# Sheet1.net
KiCad netlist of a schematic drawn in Altium Designer
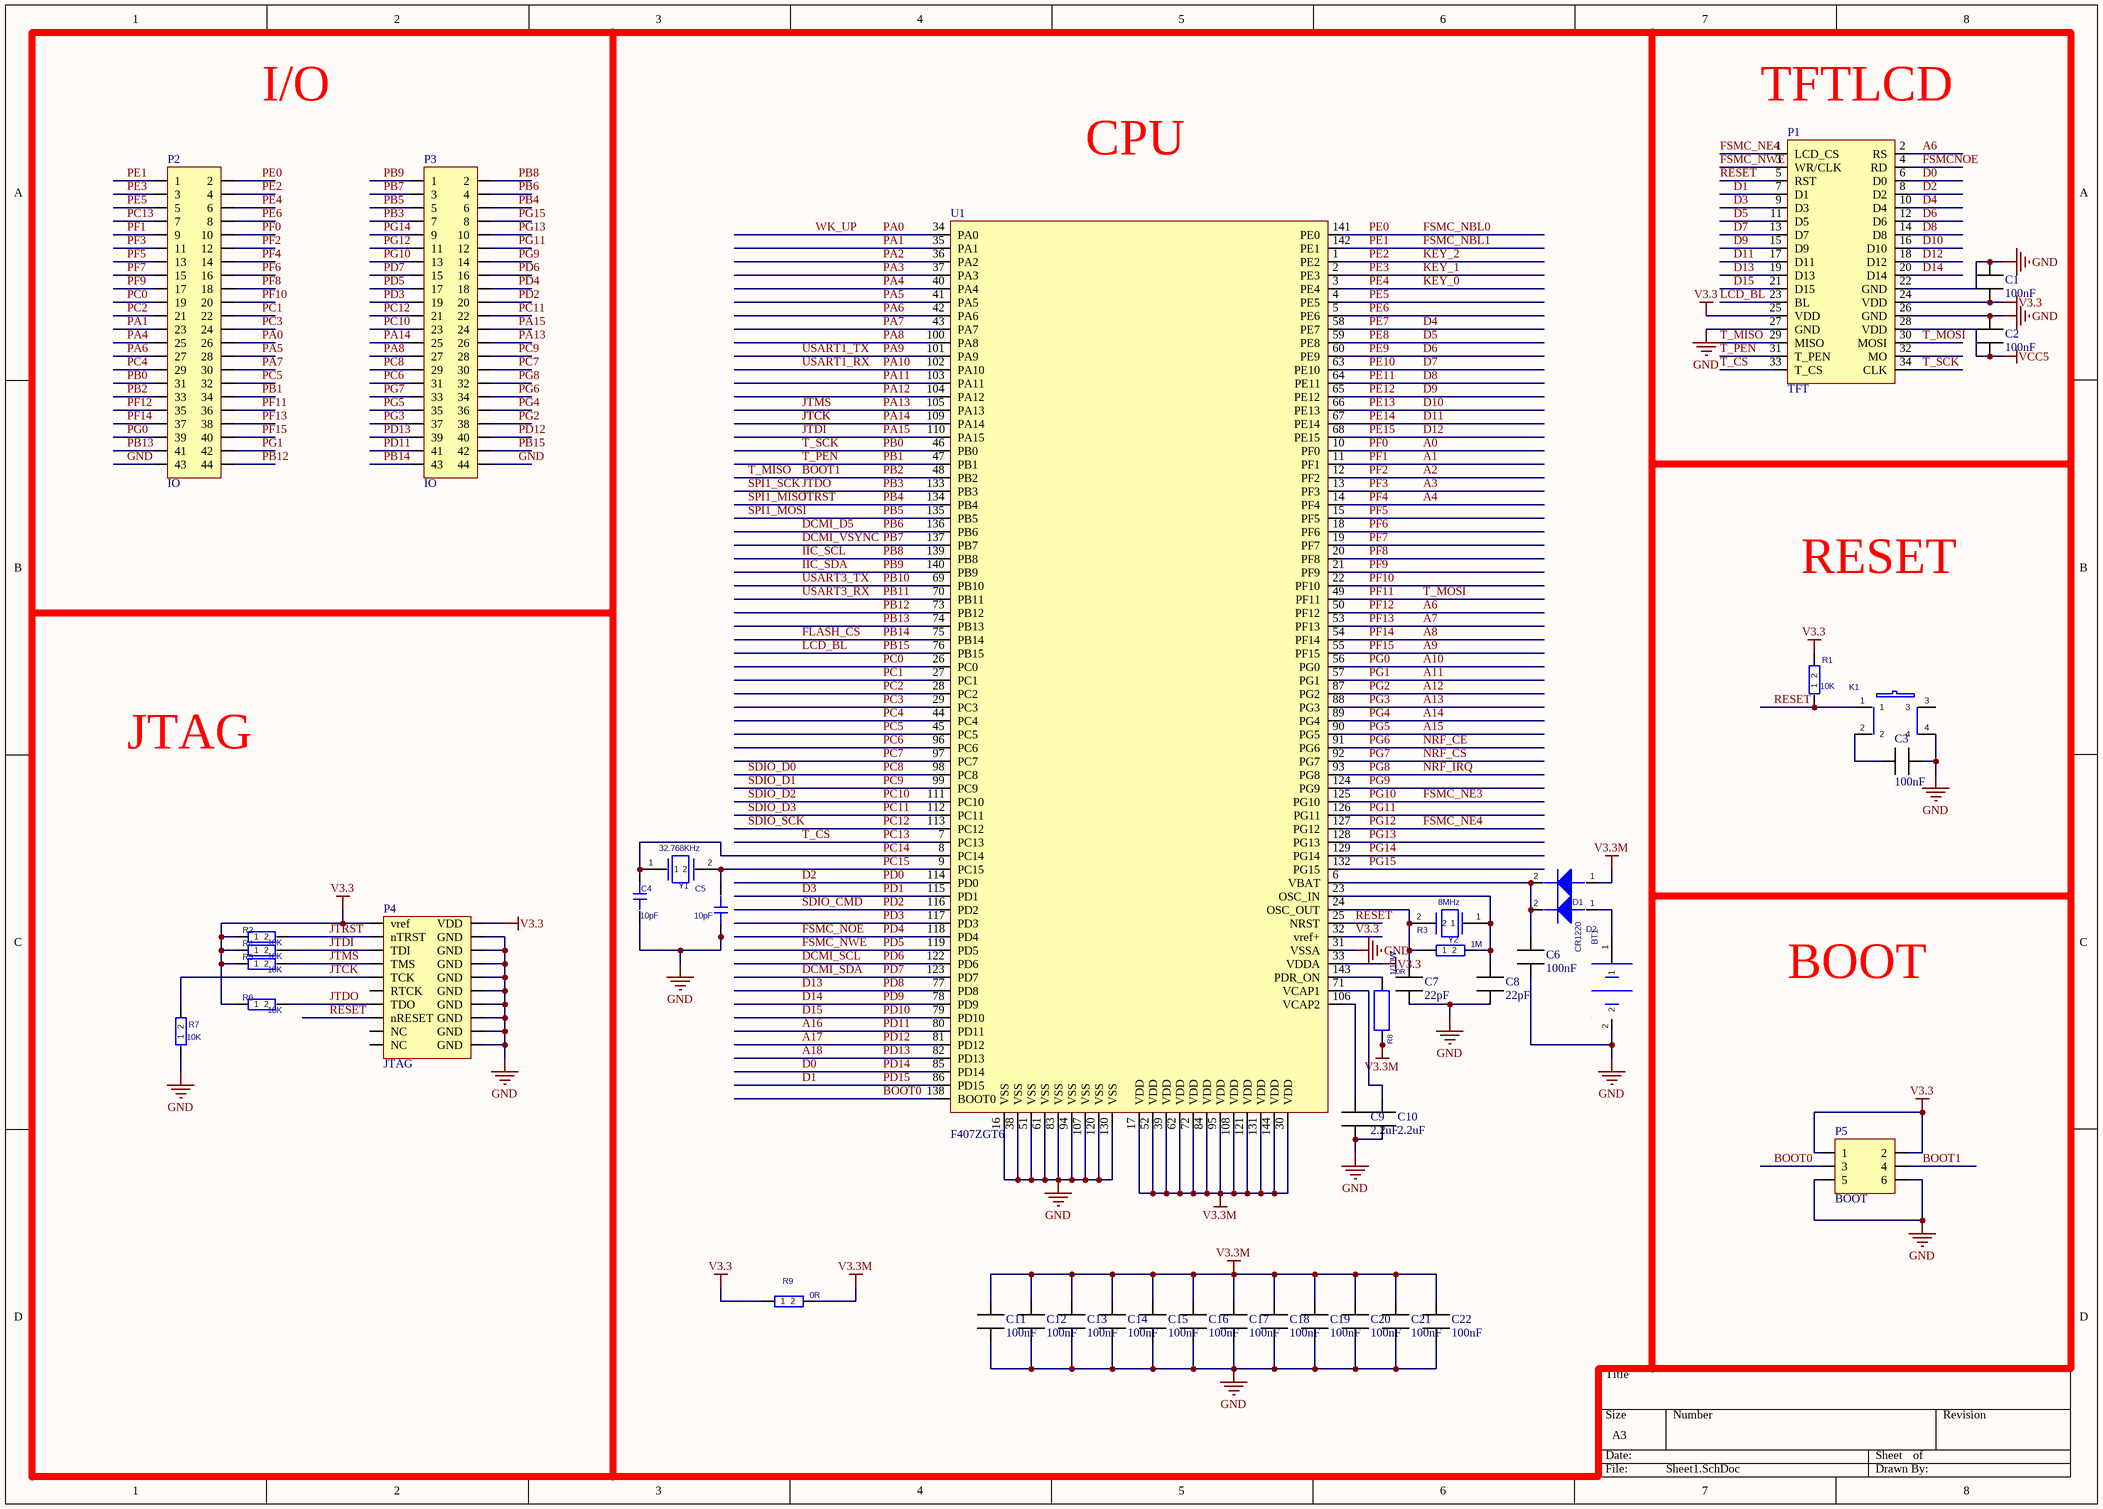
[diagram p0: Sheet1.SchDoc]

(export (version "E")
  (design (tool "Eeschema 10.0.6"))
  (components
    (comp (ref "BT1") (value "CR1220") (footprint "BATERY") (libsource (lib "F407ZGT6") (part "CR1220")))
    (comp (ref "C1") (value "100nF") (footprint "CAP_0603_FIRE") (libsource (lib "F407ZGT6") (part "CAP")))
    (comp (ref "C2") (value "100nF") (footprint "CAP_0603_FIRE") (libsource (lib "F407ZGT6") (part "CAP")))
    (comp (ref "C3") (value "100nF") (footprint "CAP_0603_FIRE") (libsource (lib "F407ZGT6") (part "CAP")))
    (comp (ref "C4")
      (value "10pF")
      (footprint "CAP_0603_FIRE")
      (description "SURFACE MOUNT CAPACITOR 0.031 X 0.061 INCHES")
      (fields (field (name "Comment") "CAP_0.1UF_0603_FIRE"))
      (libsource (lib "F407ZGT6") (part "CAP_0.1UF_0603_FIRE"))
    )
    (comp (ref "C5")
      (value "10pF")
      (footprint "CAP_0603_FIRE")
      (description "SURFACE MOUNT CAPACITOR 0.031 X 0.061 INCHES")
      (fields (field (name "Comment") "CAP_0.1UF_0603_FIRE"))
      (libsource (lib "F407ZGT6") (part "CAP_0.1UF_0603_FIRE"))
    )
    (comp (ref "C6") (value "100nF") (footprint "CAP_0603_FIRE") (libsource (lib "F407ZGT6") (part "CAP")))
    (comp (ref "C7") (value "22pF") (footprint "CAP_0603_FIRE") (libsource (lib "F407ZGT6") (part "CAP")))
    (comp (ref "C8") (value "22pF") (footprint "CAP_0603_FIRE") (libsource (lib "F407ZGT6") (part "CAP")))
    (comp (ref "C9") (value "2.2uF") (footprint "CAP_0603_FIRE") (libsource (lib "F407ZGT6") (part "CAP")))
    (comp (ref "C10") (value "2.2uF") (footprint "CAP_0603_FIRE") (libsource (lib "F407ZGT6") (part "CAP")))
    (comp (ref "C11") (value "100nF") (footprint "CAP_0603_FIRE") (libsource (lib "F407ZGT6") (part "CAP")))
    (comp (ref "C12") (value "100nF") (footprint "CAP_0603_FIRE") (libsource (lib "F407ZGT6") (part "CAP")))
    (comp (ref "C13") (value "100nF") (footprint "CAP_0603_FIRE") (libsource (lib "F407ZGT6") (part "CAP")))
    (comp (ref "C14") (value "100nF") (footprint "CAP_0603_FIRE") (libsource (lib "F407ZGT6") (part "CAP")))
    (comp (ref "C15") (value "100nF") (footprint "CAP_0603_FIRE") (libsource (lib "F407ZGT6") (part "CAP")))
    (comp (ref "C16") (value "100nF") (footprint "CAP_0603_FIRE") (libsource (lib "F407ZGT6") (part "CAP")))
    (comp (ref "C17") (value "100nF") (footprint "CAP_0603_FIRE") (libsource (lib "F407ZGT6") (part "CAP")))
    (comp (ref "C18") (value "100nF") (footprint "CAP_0603_FIRE") (libsource (lib "F407ZGT6") (part "CAP")))
    (comp (ref "C19") (value "100nF") (footprint "CAP_0603_FIRE") (libsource (lib "F407ZGT6") (part "CAP")))
    (comp (ref "C20") (value "100nF") (footprint "CAP_0603_FIRE") (libsource (lib "F407ZGT6") (part "CAP")))
    (comp (ref "C21") (value "100nF") (footprint "CAP_0603_FIRE") (libsource (lib "F407ZGT6") (part "CAP")))
    (comp (ref "C22") (value "100nF") (footprint "CAP_0603_FIRE") (libsource (lib "F407ZGT6") (part "CAP")))
    (comp (ref "D1") (value "IN4148") (footprint "DIODE_SOP") (libsource (lib "F407ZGT6") (part "IN4148")))
    (comp (ref "D2") (value "IN4148") (footprint "DIODE_SOP") (libsource (lib "F407ZGT6") (part "IN4148")))
    (comp (ref "K1") (value "KEY") (footprint "SW6.2/6.2-SMD") (libsource (lib "F407ZGT6") (part "KEY")))
    (comp (ref "P1") (value "TFT") (footprint "TFT") (libsource (lib "F407ZGT6") (part "TFT")))
    (comp (ref "P2") (value "IO") (footprint "HEAD2*22") (libsource (lib "F407ZGT6") (part "IO")))
    (comp (ref "P3") (value "IO") (footprint "HEAD2*22") (libsource (lib "F407ZGT6") (part "IO")))
    (comp (ref "P4") (value "JTAG") (footprint "FC20H") (libsource (lib "F407ZGT6") (part "JTAG")))
    (comp (ref "P5") (value "BOOT") (footprint "BOOT") (libsource (lib "F407ZGT6") (part "BOOT")))
    (comp (ref "R1")
      (value "10K")
      (footprint "RES_0603_FIRE")
      (description "0402")
      (fields (field (name "TOLERANCE") "+-5%") (field (name "Comment") "RES_1K_0603_FIRE"))
      (libsource (lib "F407ZGT6") (part "RES_1K_0603_FIRE"))
    )
    (comp (ref "R2")
      (value "10K")
      (footprint "RES_0603_FIRE")
      (description "SURFACE MOUNT RESISTOR 0.031 X 0.061 INCHES, 1/10W")
      (fields (field (name "Comment") "RES_10K_0603_FIRE"))
      (libsource (lib "F407ZGT6") (part "RES_10K_0603_FIRE"))
    )
    (comp (ref "R3")
      (value "1M")
      (footprint "RES_0603_FIRE")
      (description "0402")
      (fields (field (name "TOLERANCE") "+-5%") (field (name "Comment") "RES_1K_0603_FIRE"))
      (libsource (lib "F407ZGT6") (part "RES_1K_0603_FIRE"))
    )
    (comp (ref "R4")
      (value "10K")
      (footprint "RES_0603_FIRE")
      (description "SURFACE MOUNT RESISTOR 0.031 X 0.061 INCHES, 1/10W")
      (fields (field (name "Comment") "RES_10K_0603_FIRE"))
      (libsource (lib "F407ZGT6") (part "RES_10K_0603_FIRE"))
    )
    (comp (ref "R5")
      (value "10K")
      (footprint "RES_0603_FIRE")
      (description "SURFACE MOUNT RESISTOR 0.031 X 0.061 INCHES, 1/10W")
      (fields (field (name "Comment") "RES_10K_0603_FIRE"))
      (libsource (lib "F407ZGT6") (part "RES_10K_0603_FIRE"))
    )
    (comp (ref "R6")
      (value "10K")
      (footprint "RES_0603_FIRE")
      (description "SURFACE MOUNT RESISTOR 0.031 X 0.061 INCHES, 1/10W")
      (fields (field (name "Comment") "RES_10K_0603_FIRE"))
      (libsource (lib "F407ZGT6") (part "RES_10K_0603_FIRE"))
    )
    (comp (ref "R7")
      (value "10K")
      (footprint "RES_0603_FIRE")
      (description "SURFACE MOUNT RESISTOR 0.031 X 0.061 INCHES, 1/10W")
      (fields (field (name "Comment") "RES_10K_0603_FIRE"))
      (libsource (lib "F407ZGT6") (part "RES_10K_0603_FIRE"))
    )
    (comp (ref "R8")
      (value "0R")
      (footprint "0603")
      (description "0603, 50V, 1/10W, 5%")
      (fields
        (field (name "PART_NUMBER") "RE200045-01")
        (field (name "MFR_PART_NUMBER") "RS03K104JT")
        (field (name "POWER") "1/10W")
      )
      (libsource (lib "F407ZGT6") (part "RES-0603-0R"))
    )
    (comp (ref "R9")
      (value "0R")
      (footprint "RES_0603_FIRE")
      (description "0402")
      (fields (field (name "TOLERANCE") "+-5%") (field (name "Comment") "RES_1K_0603_FIRE"))
      (libsource (lib "F407ZGT6") (part "RES_1K_0603_FIRE"))
    )
    (comp (ref "U1")
      (value "F407ZGT6")
      (footprint "STM32F407ZGT6")
      (libsource (lib "F407ZGT6") (part "F407ZGT6"))
    )
    (comp (ref "Y1")
      (value "32.768KHz")
      (footprint "CRYS-3X8")
      (description "CRYSTAL")
      (fields (field (name "Comment") "XTAL_32.768KHZ_FIRE"))
      (libsource (lib "F407ZGT6") (part "XTAL_32.768KHZ_FIRE"))
    )
    (comp (ref "Y2")
      (value "8MHz")
      (footprint "CRYSTAL_SMD_FIRE")
      (description "CRYSTAL")
      (fields (field (name "Comment") "XTAL_8M_FIRE"))
      (libsource (lib "F407ZGT6") (part "XTAL_8M_FIRE"))
    )
  )
  (nets
    (net (code "1") (name "/A0") (class "Default")
      (node (ref "P2") (pin "10") (pinfunction "10_10") (pintype "passive"))
      (node (ref "U1") (pin "10") (pinfunction "PF0_10") (pintype "passive"))
    )
    (net (code "2") (name "/A1") (class "Default")
      (node (ref "P2") (pin "9") (pinfunction "9_9") (pintype "passive"))
      (node (ref "U1") (pin "11") (pinfunction "PF1_11") (pintype "passive"))
    )
    (net (code "3") (name "/A2") (class "Default")
      (node (ref "P2") (pin "12") (pinfunction "12_12") (pintype "passive"))
      (node (ref "U1") (pin "12") (pinfunction "PF2_12") (pintype "passive"))
    )
    (net (code "4") (name "/A3") (class "Default")
      (node (ref "P2") (pin "11") (pinfunction "11_11") (pintype "passive"))
      (node (ref "U1") (pin "13") (pinfunction "PF3_13") (pintype "passive"))
    )
    (net (code "5") (name "/A4") (class "Default")
      (node (ref "P2") (pin "14") (pinfunction "14_14") (pintype "passive"))
      (node (ref "U1") (pin "14") (pinfunction "PF4_14") (pintype "passive"))
    )
    (net (code "6") (name "/A6") (class "Default")
      (node (ref "P1") (pin "2") (pinfunction "RS_2") (pintype "passive"))
      (node (ref "P2") (pin "35") (pinfunction "35_35") (pintype "passive"))
      (node (ref "U1") (pin "50") (pinfunction "PF12_50") (pintype "passive"))
    )
    (net (code "7") (name "/A7") (class "Default")
      (node (ref "P2") (pin "38") (pinfunction "38_38") (pintype "passive"))
      (node (ref "U1") (pin "53") (pinfunction "PF13_53") (pintype "passive"))
    )
    (net (code "8") (name "/A8") (class "Default")
      (node (ref "P2") (pin "37") (pinfunction "37_37") (pintype "passive"))
      (node (ref "U1") (pin "54") (pinfunction "PF14_54") (pintype "passive"))
    )
    (net (code "9") (name "/A9") (class "Default")
      (node (ref "P2") (pin "40") (pinfunction "40_40") (pintype "passive"))
      (node (ref "U1") (pin "55") (pinfunction "PF15_55") (pintype "passive"))
    )
    (net (code "10") (name "/A10") (class "Default")
      (node (ref "P2") (pin "39") (pinfunction "39_39") (pintype "passive"))
      (node (ref "U1") (pin "56") (pinfunction "PG0_56") (pintype "passive"))
    )
    (net (code "11") (name "/A11") (class "Default")
      (node (ref "P2") (pin "42") (pinfunction "42_42") (pintype "passive"))
      (node (ref "U1") (pin "57") (pinfunction "PG1_57") (pintype "passive"))
    )
    (net (code "12") (name "/A12") (class "Default")
      (node (ref "P3") (pin "38") (pinfunction "38_38") (pintype "passive"))
      (node (ref "U1") (pin "87") (pinfunction "PG2_87") (pintype "passive"))
    )
    (net (code "13") (name "/A13") (class "Default")
      (node (ref "P3") (pin "37") (pinfunction "37_37") (pintype "passive"))
      (node (ref "U1") (pin "88") (pinfunction "PG3_88") (pintype "passive"))
    )
    (net (code "14") (name "/A14") (class "Default")
      (node (ref "P3") (pin "36") (pinfunction "36_36") (pintype "passive"))
      (node (ref "U1") (pin "89") (pinfunction "PG4_89") (pintype "passive"))
    )
    (net (code "15") (name "/A15") (class "Default")
      (node (ref "P3") (pin "35") (pinfunction "35_35") (pintype "passive"))
      (node (ref "U1") (pin "90") (pinfunction "PG5_90") (pintype "passive"))
    )
    (net (code "16") (name "/A16") (class "Default")
      (node (ref "P3") (pin "41") (pinfunction "41_41") (pintype "passive"))
      (node (ref "U1") (pin "80") (pinfunction "PD11_80") (pintype "passive"))
    )
    (net (code "17") (name "/A17") (class "Default")
      (node (ref "P3") (pin "40") (pinfunction "40_40") (pintype "passive"))
      (node (ref "U1") (pin "81") (pinfunction "PD12_81") (pintype "passive"))
    )
    (net (code "18") (name "/A18") (class "Default")
      (node (ref "P3") (pin "39") (pinfunction "39_39") (pintype "passive"))
      (node (ref "U1") (pin "82") (pinfunction "PD13_82") (pintype "passive"))
    )
    (net (code "19") (name "/BOOT0") (class "Default")
      (node (ref "P5") (pin "3") (pinfunction "3_3") (pintype "passive"))
      (node (ref "U1") (pin "138") (pinfunction "BOOT0_138") (pintype "passive"))
    )
    (net (code "20") (name "/BOOT1") (class "Default")
      (node (ref "P1") (pin "29") (pinfunction "MISO_29") (pintype "passive"))
      (node (ref "P2") (pin "33") (pinfunction "33_33") (pintype "passive"))
      (node (ref "P5") (pin "4") (pinfunction "4_4") (pintype "passive"))
      (node (ref "U1") (pin "48") (pinfunction "PB2_48") (pintype "passive"))
    )
    (net (code "21") (name "/D0") (class "Default")
      (node (ref "P1") (pin "6") (pinfunction "D0_6") (pintype "passive"))
      (node (ref "U1") (pin "85") (pinfunction "PD14_85") (pintype "passive"))
    )
    (net (code "22") (name "/D1") (class "Default")
      (node (ref "P1") (pin "7") (pinfunction "D1_7") (pintype "passive"))
      (node (ref "U1") (pin "86") (pinfunction "PD15_86") (pintype "passive"))
    )
    (net (code "23") (name "/D2") (class "Default")
      (node (ref "P1") (pin "8") (pinfunction "D2_8") (pintype "passive"))
      (node (ref "U1") (pin "114") (pinfunction "PD0_114") (pintype "passive"))
    )
    (net (code "24") (name "/D3") (class "Default")
      (node (ref "P1") (pin "9") (pinfunction "D3_9") (pintype "passive"))
      (node (ref "U1") (pin "115") (pinfunction "PD1_115") (pintype "passive"))
    )
    (net (code "25") (name "/D4") (class "Default")
      (node (ref "P1") (pin "10") (pinfunction "D4_10") (pintype "passive"))
      (node (ref "U1") (pin "58") (pinfunction "PE7_58") (pintype "passive"))
    )
    (net (code "26") (name "/D5") (class "Default")
      (node (ref "P1") (pin "11") (pinfunction "D5_11") (pintype "passive"))
      (node (ref "U1") (pin "59") (pinfunction "PE8_59") (pintype "passive"))
    )
    (net (code "27") (name "/D6") (class "Default")
      (node (ref "P1") (pin "12") (pinfunction "D6_12") (pintype "passive"))
      (node (ref "U1") (pin "60") (pinfunction "PE9_60") (pintype "passive"))
    )
    (net (code "28") (name "/D7") (class "Default")
      (node (ref "P1") (pin "13") (pinfunction "D7_13") (pintype "passive"))
      (node (ref "U1") (pin "63") (pinfunction "PE10_63") (pintype "passive"))
    )
    (net (code "29") (name "/D8") (class "Default")
      (node (ref "P1") (pin "14") (pinfunction "D8_14") (pintype "passive"))
      (node (ref "U1") (pin "64") (pinfunction "PE11_64") (pintype "passive"))
    )
    (net (code "30") (name "/D9") (class "Default")
      (node (ref "P1") (pin "15") (pinfunction "D9_15") (pintype "passive"))
      (node (ref "U1") (pin "65") (pinfunction "PE12_65") (pintype "passive"))
    )
    (net (code "31") (name "/D10") (class "Default")
      (node (ref "P1") (pin "16") (pinfunction "D10_16") (pintype "passive"))
      (node (ref "U1") (pin "66") (pinfunction "PE13_66") (pintype "passive"))
    )
    (net (code "32") (name "/D11") (class "Default")
      (node (ref "P1") (pin "17") (pinfunction "D11_17") (pintype "passive"))
      (node (ref "U1") (pin "67") (pinfunction "PE14_67") (pintype "passive"))
    )
    (net (code "33") (name "/D12") (class "Default")
      (node (ref "P1") (pin "18") (pinfunction "D12_18") (pintype "passive"))
      (node (ref "U1") (pin "68") (pinfunction "PE15_68") (pintype "passive"))
    )
    (net (code "34") (name "/D13") (class "Default")
      (node (ref "P1") (pin "19") (pinfunction "D13_19") (pintype "passive"))
      (node (ref "U1") (pin "77") (pinfunction "PD8_77") (pintype "passive"))
    )
    (net (code "35") (name "/D14") (class "Default")
      (node (ref "P1") (pin "20") (pinfunction "D14_20") (pintype "passive"))
      (node (ref "U1") (pin "78") (pinfunction "PD9_78") (pintype "passive"))
    )
    (net (code "36") (name "/D15") (class "Default")
      (node (ref "P1") (pin "21") (pinfunction "D15_21") (pintype "passive"))
      (node (ref "U1") (pin "79") (pinfunction "PD10_79") (pintype "passive"))
    )
    (net (code "37") (name "/DCMI_D5") (class "Default")
      (node (ref "P3") (pin "4") (pinfunction "4_4") (pintype "passive"))
      (node (ref "U1") (pin "136") (pinfunction "PB6_136") (pintype "passive"))
    )
    (net (code "38") (name "/DCMI_SCL") (class "Default")
      (node (ref "P3") (pin "16") (pinfunction "16_16") (pintype "passive"))
      (node (ref "U1") (pin "122") (pinfunction "PD6_122") (pintype "passive"))
    )
    (net (code "39") (name "/DCMI_SDA") (class "Default")
      (node (ref "P3") (pin "15") (pinfunction "15_15") (pintype "passive"))
      (node (ref "U1") (pin "123") (pinfunction "PD7_123") (pintype "passive"))
    )
    (net (code "40") (name "/DCMI_VSYNC") (class "Default")
      (node (ref "P3") (pin "3") (pinfunction "3_3") (pintype "passive"))
      (node (ref "U1") (pin "137") (pinfunction "PB7_137") (pintype "passive"))
    )
    (net (code "41") (name "/FLASH_CS") (class "Default")
      (node (ref "P3") (pin "43") (pinfunction "43_43") (pintype "passive"))
      (node (ref "U1") (pin "75") (pinfunction "PB14_75") (pintype "passive"))
    )
    (net (code "42") (name "/FSMCNOE") (class "Default")
      (node (ref "P1") (pin "4") (pinfunction "RD_4") (pintype "passive"))
    )
    (net (code "43") (name "/FSMC_NBL0") (class "Default")
      (node (ref "P2") (pin "2") (pinfunction "2_2") (pintype "passive"))
      (node (ref "U1") (pin "141") (pinfunction "PE0_141") (pintype "passive"))
    )
    (net (code "44") (name "/FSMC_NBL1") (class "Default")
      (node (ref "P2") (pin "1") (pinfunction "1_1") (pintype "passive"))
      (node (ref "U1") (pin "142") (pinfunction "PE1_142") (pintype "passive"))
    )
    (net (code "45") (name "/FSMC_NE3") (class "Default")
      (node (ref "P3") (pin "13") (pinfunction "13_13") (pintype "passive"))
      (node (ref "U1") (pin "125") (pinfunction "PG10_125") (pintype "passive"))
    )
    (net (code "46") (name "/FSMC_NE4") (class "Default")
      (node (ref "P1") (pin "1") (pinfunction "LCD_CS_1") (pintype "passive"))
      (node (ref "P3") (pin "11") (pinfunction "11_11") (pintype "passive"))
      (node (ref "U1") (pin "127") (pinfunction "PG12_127") (pintype "passive"))
    )
    (net (code "47") (name "/FSMC_NOE") (class "Default")
      (node (ref "P3") (pin "18") (pinfunction "18_18") (pintype "passive"))
      (node (ref "U1") (pin "118") (pinfunction "PD4_118") (pintype "passive"))
    )
    (net (code "48") (name "/FSMC_NWE") (class "Default")
      (node (ref "P1") (pin "3") (pinfunction "WR/CLK_3") (pintype "passive"))
      (node (ref "P3") (pin "17") (pinfunction "17_17") (pintype "passive"))
      (node (ref "U1") (pin "119") (pinfunction "PD5_119") (pintype "passive"))
    )
    (net (code "49") (name "/IIC_SCL") (class "Default")
      (node (ref "P3") (pin "2") (pinfunction "2_2") (pintype "passive"))
      (node (ref "U1") (pin "139") (pinfunction "PB8_139") (pintype "passive"))
    )
    (net (code "50") (name "/IIC_SDA") (class "Default")
      (node (ref "P3") (pin "1") (pinfunction "1_1") (pintype "passive"))
      (node (ref "U1") (pin "140") (pinfunction "PB9_140") (pintype "passive"))
    )
    (net (code "51") (name "/JTCK") (class "Default")
      (node (ref "P3") (pin "25") (pinfunction "25_25") (pintype "passive"))
      (node (ref "P4") (pin "9") (pinfunction "TCK_9") (pintype "passive"))
      (node (ref "R7") (pin "2") (pinfunction "2_2") (pintype "passive"))
      (node (ref "U1") (pin "109") (pinfunction "PA14_109") (pintype "passive"))
    )
    (net (code "52") (name "/JTDI") (class "Default")
      (node (ref "P3") (pin "24") (pinfunction "24_24") (pintype "passive"))
      (node (ref "P4") (pin "5") (pinfunction "TDI_5") (pintype "passive"))
      (node (ref "R4") (pin "2") (pinfunction "2_2") (pintype "passive"))
      (node (ref "U1") (pin "110") (pinfunction "PA15_110") (pintype "passive"))
    )
    (net (code "53") (name "/JTDO") (class "Default")
      (node (ref "P3") (pin "7") (pinfunction "7_7") (pintype "passive"))
      (node (ref "P4") (pin "13") (pinfunction "TDO_13") (pintype "passive"))
      (node (ref "R6") (pin "2") (pinfunction "2_2") (pintype "passive"))
      (node (ref "U1") (pin "133") (pinfunction "PB3_133") (pintype "passive"))
    )
    (net (code "54") (name "/JTMS") (class "Default")
      (node (ref "P3") (pin "26") (pinfunction "26_26") (pintype "passive"))
      (node (ref "P4") (pin "7") (pinfunction "TMS_7") (pintype "passive"))
      (node (ref "R5") (pin "2") (pinfunction "2_2") (pintype "passive"))
      (node (ref "U1") (pin "105") (pinfunction "PA13_105") (pintype "passive"))
    )
    (net (code "55") (name "/JTRST") (class "Default")
      (node (ref "P3") (pin "6") (pinfunction "6_6") (pintype "passive"))
      (node (ref "P4") (pin "3") (pinfunction "nTRST_3") (pintype "passive"))
      (node (ref "R2") (pin "2") (pinfunction "2_2") (pintype "passive"))
      (node (ref "U1") (pin "134") (pinfunction "PB4_134") (pintype "passive"))
    )
    (net (code "56") (name "/KEY_0") (class "Default")
      (node (ref "P2") (pin "6") (pinfunction "6_6") (pintype "passive"))
      (node (ref "U1") (pin "3") (pinfunction "PE4_3") (pintype "passive"))
    )
    (net (code "57") (name "/KEY_1") (class "Default")
      (node (ref "P2") (pin "3") (pinfunction "3_3") (pintype "passive"))
      (node (ref "U1") (pin "2") (pinfunction "PE3_2") (pintype "passive"))
    )
    (net (code "58") (name "/KEY_2") (class "Default")
      (node (ref "P2") (pin "4") (pinfunction "4_4") (pintype "passive"))
      (node (ref "U1") (pin "1") (pinfunction "PE2_1") (pintype "passive"))
    )
    (net (code "59") (name "/LCD_BL") (class "Default")
      (node (ref "P1") (pin "23") (pinfunction "BL_23") (pintype "passive"))
      (node (ref "P3") (pin "42") (pinfunction "42_42") (pintype "passive"))
      (node (ref "U1") (pin "76") (pinfunction "PB15_76") (pintype "passive"))
    )
    (net (code "60") (name "/NRF_CE") (class "Default")
      (node (ref "P3") (pin "34") (pinfunction "34_34") (pintype "passive"))
      (node (ref "U1") (pin "91") (pinfunction "PG6_91") (pintype "passive"))
    )
    (net (code "61") (name "/NRF_CS") (class "Default")
      (node (ref "P3") (pin "33") (pinfunction "33_33") (pintype "passive"))
      (node (ref "U1") (pin "92") (pinfunction "PG7_92") (pintype "passive"))
    )
    (net (code "62") (name "/NRF_IRQ") (class "Default")
      (node (ref "P3") (pin "32") (pinfunction "32_32") (pintype "passive"))
      (node (ref "U1") (pin "93") (pinfunction "PG8_93") (pintype "passive"))
    )
    (net (code "63") (name "/PA0") (class "Default")
      (node (ref "P2") (pin "26") (pinfunction "26_26") (pintype "passive"))
      (node (ref "U1") (pin "34") (pinfunction "PA0_34") (pintype "passive"))
    )
    (net (code "64") (name "/PA1") (class "Default")
      (node (ref "P2") (pin "23") (pinfunction "23_23") (pintype "passive"))
      (node (ref "U1") (pin "35") (pinfunction "PA1_35") (pintype "passive"))
    )
    (net (code "65") (name "/PA2") (class "Default")
      (node (ref "U1") (pin "36") (pinfunction "PA2_36") (pintype "passive"))
    )
    (net (code "66") (name "/PA3") (class "Default")
      (node (ref "U1") (pin "37") (pinfunction "PA3_37") (pintype "passive"))
    )
    (net (code "67") (name "/PA4") (class "Default")
      (node (ref "P2") (pin "25") (pinfunction "25_25") (pintype "passive"))
      (node (ref "U1") (pin "40") (pinfunction "PA4_40") (pintype "passive"))
    )
    (net (code "68") (name "/PA5") (class "Default")
      (node (ref "P2") (pin "28") (pinfunction "28_28") (pintype "passive"))
      (node (ref "U1") (pin "41") (pinfunction "PA5_41") (pintype "passive"))
    )
    (net (code "69") (name "/PA6") (class "Default")
      (node (ref "P2") (pin "27") (pinfunction "27_27") (pintype "passive"))
      (node (ref "U1") (pin "42") (pinfunction "PA6_42") (pintype "passive"))
    )
    (net (code "70") (name "/PA7") (class "Default")
      (node (ref "P2") (pin "30") (pinfunction "30_30") (pintype "passive"))
      (node (ref "U1") (pin "43") (pinfunction "PA7_43") (pintype "passive"))
    )
    (net (code "71") (name "/PA8") (class "Default")
      (node (ref "P3") (pin "27") (pinfunction "27_27") (pintype "passive"))
      (node (ref "U1") (pin "100") (pinfunction "PA8_100") (pintype "passive"))
    )
    (net (code "72") (name "/PA9") (class "Default")
      (node (ref "U1") (pin "101") (pinfunction "PA9_101") (pintype "passive"))
    )
    (net (code "73") (name "/PA10") (class "Default")
      (node (ref "U1") (pin "102") (pinfunction "PA10_102") (pintype "passive"))
    )
    (net (code "74") (name "/PA11") (class "Default")
      (node (ref "U1") (pin "103") (pinfunction "PA11_103") (pintype "passive"))
    )
    (net (code "75") (name "/PA12") (class "Default")
      (node (ref "U1") (pin "104") (pinfunction "PA12_104") (pintype "passive"))
    )
    (net (code "76") (name "/PB0") (class "Default")
      (node (ref "P1") (pin "34") (pinfunction "CLK_34") (pintype "passive"))
      (node (ref "P2") (pin "31") (pinfunction "31_31") (pintype "passive"))
      (node (ref "U1") (pin "46") (pinfunction "PB0_46") (pintype "passive"))
    )
    (net (code "77") (name "/PB1") (class "Default")
      (node (ref "P1") (pin "31") (pinfunction "T_PEN_31") (pintype "passive"))
      (node (ref "P2") (pin "34") (pinfunction "34_34") (pintype "passive"))
      (node (ref "U1") (pin "47") (pinfunction "PB1_47") (pintype "passive"))
    )
    (net (code "78") (name "/PB5") (class "Default")
      (node (ref "P3") (pin "5") (pinfunction "5_5") (pintype "passive"))
      (node (ref "U1") (pin "135") (pinfunction "PB5_135") (pintype "passive"))
    )
    (net (code "79") (name "/PB10") (class "Default")
      (node (ref "U1") (pin "69") (pinfunction "PB10_69") (pintype "passive"))
    )
    (net (code "80") (name "/PB11") (class "Default")
      (node (ref "U1") (pin "70") (pinfunction "PB11_70") (pintype "passive"))
    )
    (net (code "81") (name "/PB12") (class "Default")
      (node (ref "P2") (pin "44") (pinfunction "44_44") (pintype "passive"))
      (node (ref "U1") (pin "73") (pinfunction "PB12_73") (pintype "passive"))
    )
    (net (code "82") (name "/PB13") (class "Default")
      (node (ref "P2") (pin "41") (pinfunction "41_41") (pintype "passive"))
      (node (ref "U1") (pin "74") (pinfunction "PB13_74") (pintype "passive"))
    )
    (net (code "83") (name "/PC0") (class "Default")
      (node (ref "P2") (pin "19") (pinfunction "19_19") (pintype "passive"))
      (node (ref "U1") (pin "26") (pinfunction "PC0_26") (pintype "passive"))
    )
    (net (code "84") (name "/PC1") (class "Default")
      (node (ref "P2") (pin "22") (pinfunction "22_22") (pintype "passive"))
      (node (ref "U1") (pin "27") (pinfunction "PC1_27") (pintype "passive"))
    )
    (net (code "85") (name "/PC2") (class "Default")
      (node (ref "P2") (pin "21") (pinfunction "21_21") (pintype "passive"))
      (node (ref "U1") (pin "28") (pinfunction "PC2_28") (pintype "passive"))
    )
    (net (code "86") (name "/PC3") (class "Default")
      (node (ref "P2") (pin "24") (pinfunction "24_24") (pintype "passive"))
      (node (ref "U1") (pin "29") (pinfunction "PC3_29") (pintype "passive"))
    )
    (net (code "87") (name "/PC4") (class "Default")
      (node (ref "P2") (pin "29") (pinfunction "29_29") (pintype "passive"))
      (node (ref "U1") (pin "44") (pinfunction "PC4_44") (pintype "passive"))
    )
    (net (code "88") (name "/PC5") (class "Default")
      (node (ref "P2") (pin "32") (pinfunction "32_32") (pintype "passive"))
      (node (ref "U1") (pin "45") (pinfunction "PC5_45") (pintype "passive"))
    )
    (net (code "89") (name "/PC6") (class "Default")
      (node (ref "P3") (pin "31") (pinfunction "31_31") (pintype "passive"))
      (node (ref "U1") (pin "96") (pinfunction "PC6_96") (pintype "passive"))
    )
    (net (code "90") (name "/PC7") (class "Default")
      (node (ref "P3") (pin "30") (pinfunction "30_30") (pintype "passive"))
      (node (ref "U1") (pin "97") (pinfunction "PC7_97") (pintype "passive"))
    )
    (net (code "91") (name "/PC8") (class "Default")
      (node (ref "P3") (pin "29") (pinfunction "29_29") (pintype "passive"))
      (node (ref "U1") (pin "98") (pinfunction "PC8_98") (pintype "passive"))
    )
    (net (code "92") (name "/PC9") (class "Default")
      (node (ref "P3") (pin "28") (pinfunction "28_28") (pintype "passive"))
      (node (ref "U1") (pin "99") (pinfunction "PC9_99") (pintype "passive"))
    )
    (net (code "93") (name "/PC10") (class "Default")
      (node (ref "P3") (pin "23") (pinfunction "23_23") (pintype "passive"))
      (node (ref "U1") (pin "111") (pinfunction "PC10_111") (pintype "passive"))
    )
    (net (code "94") (name "/PC11") (class "Default")
      (node (ref "P3") (pin "22") (pinfunction "22_22") (pintype "passive"))
      (node (ref "U1") (pin "112") (pinfunction "PC11_112") (pintype "passive"))
    )
    (net (code "95") (name "/PC12") (class "Default")
      (node (ref "P3") (pin "21") (pinfunction "21_21") (pintype "passive"))
      (node (ref "U1") (pin "113") (pinfunction "PC12_113") (pintype "passive"))
    )
    (net (code "96") (name "/PC13") (class "Default")
      (node (ref "P1") (pin "33") (pinfunction "T_CS_33") (pintype "passive"))
      (node (ref "P2") (pin "7") (pinfunction "7_7") (pintype "passive"))
      (node (ref "U1") (pin "7") (pinfunction "PC13_7") (pintype "passive"))
    )
    (net (code "97") (name "/PC14") (class "Default")
      (node (ref "C4") (pin "2") (pinfunction "2_2") (pintype "passive"))
      (node (ref "U1") (pin "8") (pinfunction "PC14_8") (pintype "passive"))
      (node (ref "Y1") (pin "1") (pinfunction "1_1") (pintype "passive"))
    )
    (net (code "98") (name "/PC15") (class "Default")
      (node (ref "C5") (pin "2") (pinfunction "2_2") (pintype "passive"))
      (node (ref "U1") (pin "9") (pinfunction "PC15_9") (pintype "passive"))
      (node (ref "Y1") (pin "2") (pinfunction "2_2") (pintype "passive"))
    )
    (net (code "99") (name "/PD2") (class "Default")
      (node (ref "P3") (pin "20") (pinfunction "20_20") (pintype "passive"))
      (node (ref "U1") (pin "116") (pinfunction "PD2_116") (pintype "passive"))
    )
    (net (code "100") (name "/PD3") (class "Default")
      (node (ref "P3") (pin "19") (pinfunction "19_19") (pintype "passive"))
      (node (ref "U1") (pin "117") (pinfunction "PD3_117") (pintype "passive"))
    )
    (net (code "101") (name "/PE5") (class "Default")
      (node (ref "P2") (pin "5") (pinfunction "5_5") (pintype "passive"))
      (node (ref "U1") (pin "4") (pinfunction "PE5_4") (pintype "passive"))
    )
    (net (code "102") (name "/PE6") (class "Default")
      (node (ref "P2") (pin "8") (pinfunction "8_8") (pintype "passive"))
      (node (ref "U1") (pin "5") (pinfunction "PE6_5") (pintype "passive"))
    )
    (net (code "103") (name "/PF5") (class "Default")
      (node (ref "P2") (pin "13") (pinfunction "13_13") (pintype "passive"))
      (node (ref "U1") (pin "15") (pinfunction "PF5_15") (pintype "passive"))
    )
    (net (code "104") (name "/PF6") (class "Default")
      (node (ref "P2") (pin "16") (pinfunction "16_16") (pintype "passive"))
      (node (ref "U1") (pin "18") (pinfunction "PF6_18") (pintype "passive"))
    )
    (net (code "105") (name "/PF7") (class "Default")
      (node (ref "P2") (pin "15") (pinfunction "15_15") (pintype "passive"))
      (node (ref "U1") (pin "19") (pinfunction "PF7_19") (pintype "passive"))
    )
    (net (code "106") (name "/PF8") (class "Default")
      (node (ref "P2") (pin "18") (pinfunction "18_18") (pintype "passive"))
      (node (ref "U1") (pin "20") (pinfunction "PF8_20") (pintype "passive"))
    )
    (net (code "107") (name "/PF9") (class "Default")
      (node (ref "P2") (pin "17") (pinfunction "17_17") (pintype "passive"))
      (node (ref "U1") (pin "21") (pinfunction "PF9_21") (pintype "passive"))
    )
    (net (code "108") (name "/PF10") (class "Default")
      (node (ref "P2") (pin "20") (pinfunction "20_20") (pintype "passive"))
      (node (ref "U1") (pin "22") (pinfunction "PF10_22") (pintype "passive"))
    )
    (net (code "109") (name "/PF11") (class "Default")
      (node (ref "P1") (pin "30") (pinfunction "MOSI_30") (pintype "passive"))
      (node (ref "P2") (pin "36") (pinfunction "36_36") (pintype "passive"))
      (node (ref "U1") (pin "49") (pinfunction "PF11_49") (pintype "passive"))
    )
    (net (code "110") (name "/PG9") (class "Default")
      (node (ref "P3") (pin "14") (pinfunction "14_14") (pintype "passive"))
      (node (ref "U1") (pin "124") (pinfunction "PG9_124") (pintype "passive"))
    )
    (net (code "111") (name "/PG11") (class "Default")
      (node (ref "P3") (pin "12") (pinfunction "12_12") (pintype "passive"))
      (node (ref "U1") (pin "126") (pinfunction "PG11_126") (pintype "passive"))
    )
    (net (code "112") (name "/PG13") (class "Default")
      (node (ref "P3") (pin "10") (pinfunction "10_10") (pintype "passive"))
      (node (ref "U1") (pin "128") (pinfunction "PG13_128") (pintype "passive"))
    )
    (net (code "113") (name "/PG14") (class "Default")
      (node (ref "P3") (pin "9") (pinfunction "9_9") (pintype "passive"))
      (node (ref "U1") (pin "129") (pinfunction "PG14_129") (pintype "passive"))
    )
    (net (code "114") (name "/PG15") (class "Default")
      (node (ref "P3") (pin "8") (pinfunction "8_8") (pintype "passive"))
      (node (ref "U1") (pin "132") (pinfunction "PG15_132") (pintype "passive"))
    )
    (net (code "115") (name "/RESET") (class "Default")
      (node (ref "K1") (pin "1") (pinfunction "1_1") (pintype "passive"))
      (node (ref "P1") (pin "5") (pinfunction "RST_5") (pintype "passive"))
      (node (ref "P4") (pin "15") (pinfunction "nRESET_15") (pintype "passive"))
      (node (ref "R1") (pin "1") (pinfunction "1_1") (pintype "passive"))
      (node (ref "U1") (pin "25") (pinfunction "NRST_25") (pintype "passive"))
    )
    (net (code "116") (name "GND") (class "Default")
      (node (ref "BT1") (pin "2") (pinfunction "2_2") (pintype "passive"))
      (node (ref "C1") (pin "2") (pinfunction "2_2") (pintype "passive"))
      (node (ref "C10") (pin "1") (pinfunction "1_1") (pintype "passive"))
      (node (ref "C11") (pin "1") (pinfunction "1_1") (pintype "passive"))
      (node (ref "C12") (pin "1") (pinfunction "1_1") (pintype "passive"))
      (node (ref "C13") (pin "1") (pinfunction "1_1") (pintype "passive"))
      (node (ref "C14") (pin "1") (pinfunction "1_1") (pintype "passive"))
      (node (ref "C15") (pin "1") (pinfunction "1_1") (pintype "passive"))
      (node (ref "C16") (pin "1") (pinfunction "1_1") (pintype "passive"))
      (node (ref "C17") (pin "1") (pinfunction "1_1") (pintype "passive"))
      (node (ref "C18") (pin "1") (pinfunction "1_1") (pintype "passive"))
      (node (ref "C19") (pin "1") (pinfunction "1_1") (pintype "passive"))
      (node (ref "C2") (pin "2") (pinfunction "2_2") (pintype "passive"))
      (node (ref "C20") (pin "1") (pinfunction "1_1") (pintype "passive"))
      (node (ref "C21") (pin "1") (pinfunction "1_1") (pintype "passive"))
      (node (ref "C22") (pin "1") (pinfunction "1_1") (pintype "passive"))
      (node (ref "C3") (pin "1") (pinfunction "1_1") (pintype "passive"))
      (node (ref "C4") (pin "1") (pinfunction "1_1") (pintype "passive"))
      (node (ref "C5") (pin "1") (pinfunction "1_1") (pintype "passive"))
      (node (ref "C6") (pin "1") (pinfunction "1_1") (pintype "passive"))
      (node (ref "C7") (pin "1") (pinfunction "1_1") (pintype "passive"))
      (node (ref "C8") (pin "1") (pinfunction "1_1") (pintype "passive"))
      (node (ref "C9") (pin "1") (pinfunction "1_1") (pintype "passive"))
      (node (ref "K1") (pin "4") (pinfunction "4_4") (pintype "passive"))
      (node (ref "P1") (pin "22") (pinfunction "GND_22") (pintype "passive"))
      (node (ref "P1") (pin "26") (pinfunction "GND_26") (pintype "passive"))
      (node (ref "P1") (pin "27") (pinfunction "GND_27") (pintype "passive"))
      (node (ref "P2") (pin "43") (pinfunction "43_43") (pintype "passive"))
      (node (ref "P3") (pin "44") (pinfunction "44_44") (pintype "passive"))
      (node (ref "P4") (pin "10") (pinfunction "GND_10") (pintype "passive"))
      (node (ref "P4") (pin "12") (pinfunction "GND_12") (pintype "passive"))
      (node (ref "P4") (pin "14") (pinfunction "GND_14") (pintype "passive"))
      (node (ref "P4") (pin "16") (pinfunction "GND_16") (pintype "passive"))
      (node (ref "P4") (pin "18") (pinfunction "GND_18") (pintype "passive"))
      (node (ref "P4") (pin "20") (pinfunction "GND_20") (pintype "passive"))
      (node (ref "P4") (pin "4") (pinfunction "GND_4") (pintype "passive"))
      (node (ref "P4") (pin "6") (pinfunction "GND_6") (pintype "passive"))
      (node (ref "P4") (pin "8") (pinfunction "GND_8") (pintype "passive"))
      (node (ref "P5") (pin "5") (pinfunction "5_5") (pintype "passive"))
      (node (ref "P5") (pin "6") (pinfunction "6_6") (pintype "passive"))
      (node (ref "R7") (pin "1") (pinfunction "1_1") (pintype "passive"))
      (node (ref "U1") (pin "107") (pinfunction "VSS_107") (pintype "passive"))
      (node (ref "U1") (pin "120") (pinfunction "VSS_120") (pintype "passive"))
      (node (ref "U1") (pin "130") (pinfunction "VSS_130") (pintype "passive"))
      (node (ref "U1") (pin "16") (pinfunction "VSS_16") (pintype "passive"))
      (node (ref "U1") (pin "31") (pinfunction "VSSA_31") (pintype "passive"))
      (node (ref "U1") (pin "38") (pinfunction "VSS_38") (pintype "passive"))
      (node (ref "U1") (pin "51") (pinfunction "VSS_51") (pintype "passive"))
      (node (ref "U1") (pin "61") (pinfunction "VSS_61") (pintype "passive"))
      (node (ref "U1") (pin "83") (pinfunction "VSS_83") (pintype "passive"))
      (node (ref "U1") (pin "94") (pinfunction "VSS_94") (pintype "passive"))
    )
    (net (code "117") (name "Net-(C3-Pad2)") (class "Default")
      (node (ref "C3") (pin "2") (pinfunction "2_2") (pintype "passive"))
      (node (ref "K1") (pin "2") (pinfunction "2_2") (pintype "passive"))
    )
    (net (code "118") (name "Net-(D1--)") (class "Default")
      (node (ref "C6") (pin "2") (pinfunction "2_2") (pintype "passive"))
      (node (ref "D1") (pin "2") (pinfunction "-_2") (pintype "passive"))
      (node (ref "D2") (pin "2") (pinfunction "-_2") (pintype "passive"))
      (node (ref "U1") (pin "6") (pinfunction "VBAT_6") (pintype "passive"))
    )
    (net (code "119") (name "Net-(D2-+)") (class "Default")
      (node (ref "BT1") (pin "1") (pinfunction "1_1") (pintype "passive"))
      (node (ref "D2") (pin "1") (pinfunction "+_1") (pintype "passive"))
    )
    (net (code "120") (name "Net-(U1-OSC_IN)") (class "Default")
      (node (ref "C8") (pin "2") (pinfunction "2_2") (pintype "passive"))
      (node (ref "R3") (pin "2") (pinfunction "2_2") (pintype "passive"))
      (node (ref "U1") (pin "23") (pinfunction "OSC_IN_23") (pintype "passive"))
      (node (ref "Y2") (pin "1") (pinfunction "1_1") (pintype "passive"))
    )
    (net (code "121") (name "Net-(U1-OSC_OUT)") (class "Default")
      (node (ref "C7") (pin "2") (pinfunction "2_2") (pintype "passive"))
      (node (ref "R3") (pin "1") (pinfunction "1_1") (pintype "passive"))
      (node (ref "U1") (pin "24") (pinfunction "OSC_OUT_24") (pintype "passive"))
      (node (ref "Y2") (pin "2") (pinfunction "2_2") (pintype "passive"))
    )
    (net (code "122") (name "Net-(U1-PDR_ON)") (class "Default")
      (node (ref "R8") (pin "2") (pinfunction "2_2") (pintype "passive"))
      (node (ref "U1") (pin "143") (pinfunction "PDR_ON_143") (pintype "passive"))
    )
    (net (code "123") (name "Net-(U1-VCAP1)") (class "Default")
      (node (ref "C10") (pin "2") (pinfunction "2_2") (pintype "passive"))
      (node (ref "U1") (pin "71") (pinfunction "VCAP1_71") (pintype "passive"))
    )
    (net (code "124") (name "Net-(U1-VCAP2)") (class "Default")
      (node (ref "C9") (pin "2") (pinfunction "2_2") (pintype "passive"))
      (node (ref "U1") (pin "106") (pinfunction "VCAP2_106") (pintype "passive"))
    )
    (net (code "125") (name "V3.3") (class "Default")
      (node (ref "C1") (pin "1") (pinfunction "1_1") (pintype "passive"))
      (node (ref "P1") (pin "24") (pinfunction "VDD_24") (pintype "passive"))
      (node (ref "P1") (pin "25") (pinfunction "VDD_25") (pintype "passive"))
      (node (ref "P4") (pin "1") (pinfunction "vref_1") (pintype "passive"))
      (node (ref "P4") (pin "2") (pinfunction "VDD_2") (pintype "passive"))
      (node (ref "P5") (pin "1") (pinfunction "1_1") (pintype "passive"))
      (node (ref "P5") (pin "2") (pinfunction "2_2") (pintype "passive"))
      (node (ref "R1") (pin "2") (pinfunction "2_2") (pintype "passive"))
      (node (ref "R2") (pin "1") (pinfunction "1_1") (pintype "passive"))
      (node (ref "R4") (pin "1") (pinfunction "1_1") (pintype "passive"))
      (node (ref "R5") (pin "1") (pinfunction "1_1") (pintype "passive"))
      (node (ref "R6") (pin "1") (pinfunction "1_1") (pintype "passive"))
      (node (ref "R9") (pin "1") (pinfunction "1_1") (pintype "passive"))
      (node (ref "U1") (pin "32") (pinfunction "vref+_32") (pintype "passive"))
      (node (ref "U1") (pin "33") (pinfunction "VDDA_33") (pintype "passive"))
    )
    (net (code "126") (name "V3.3M") (class "Default")
      (node (ref "C11") (pin "2") (pinfunction "2_2") (pintype "passive"))
      (node (ref "C12") (pin "2") (pinfunction "2_2") (pintype "passive"))
      (node (ref "C13") (pin "2") (pinfunction "2_2") (pintype "passive"))
      (node (ref "C14") (pin "2") (pinfunction "2_2") (pintype "passive"))
      (node (ref "C15") (pin "2") (pinfunction "2_2") (pintype "passive"))
      (node (ref "C16") (pin "2") (pinfunction "2_2") (pintype "passive"))
      (node (ref "C17") (pin "2") (pinfunction "2_2") (pintype "passive"))
      (node (ref "C18") (pin "2") (pinfunction "2_2") (pintype "passive"))
      (node (ref "C19") (pin "2") (pinfunction "2_2") (pintype "passive"))
      (node (ref "C20") (pin "2") (pinfunction "2_2") (pintype "passive"))
      (node (ref "C21") (pin "2") (pinfunction "2_2") (pintype "passive"))
      (node (ref "C22") (pin "2") (pinfunction "2_2") (pintype "passive"))
      (node (ref "D1") (pin "1") (pinfunction "+_1") (pintype "passive"))
      (node (ref "R8") (pin "1") (pinfunction "1_1") (pintype "passive"))
      (node (ref "R9") (pin "2") (pinfunction "2_2") (pintype "passive"))
      (node (ref "U1") (pin "108") (pinfunction "VDD_108") (pintype "passive"))
      (node (ref "U1") (pin "121") (pinfunction "VDD_121") (pintype "passive"))
      (node (ref "U1") (pin "131") (pinfunction "VDD_131") (pintype "passive"))
      (node (ref "U1") (pin "144") (pinfunction "VDD_144") (pintype "passive"))
      (node (ref "U1") (pin "17") (pinfunction "VDD_17") (pintype "passive"))
      (node (ref "U1") (pin "30") (pinfunction "VDD_30") (pintype "passive"))
      (node (ref "U1") (pin "39") (pinfunction "VDD_39") (pintype "passive"))
      (node (ref "U1") (pin "52") (pinfunction "VDD_52") (pintype "passive"))
      (node (ref "U1") (pin "62") (pinfunction "VDD_62") (pintype "passive"))
      (node (ref "U1") (pin "72") (pinfunction "VDD_72") (pintype "passive"))
      (node (ref "U1") (pin "84") (pinfunction "VDD_84") (pintype "passive"))
      (node (ref "U1") (pin "95") (pinfunction "VDD_95") (pintype "passive"))
    )
    (net (code "127") (name "VCC5") (class "Default")
      (node (ref "C2") (pin "1") (pinfunction "1_1") (pintype "passive"))
      (node (ref "P1") (pin "28") (pinfunction "VDD_28") (pintype "passive"))
    )
    (net (code "128") (name "unconnected-(K1-Pad3)") (class "Default")
      (node (ref "K1") (pin "3") (pinfunction "3_3") (pintype "passive"))
    )
    (net (code "129") (name "unconnected-(P1-MO-Pad32)") (class "Default")
      (node (ref "P1") (pin "32") (pinfunction "MO_32") (pintype "passive"))
    )
    (net (code "130") (name "unconnected-(P4-NC-Pad17)") (class "Default")
      (node (ref "P4") (pin "17") (pinfunction "NC_17") (pintype "passive"))
    )
    (net (code "131") (name "unconnected-(P4-NC-Pad19)") (class "Default")
      (node (ref "P4") (pin "19") (pinfunction "NC_19") (pintype "passive"))
    )
    (net (code "132") (name "unconnected-(P4-RTCK-Pad11)") (class "Default")
      (node (ref "P4") (pin "11") (pinfunction "RTCK_11") (pintype "passive"))
    )
  )
)
